# HALF_WAVE_WITH_WITHOUT_FILTER_PCB.net
KiCad netlist of a schematic drawn in EasyEDA
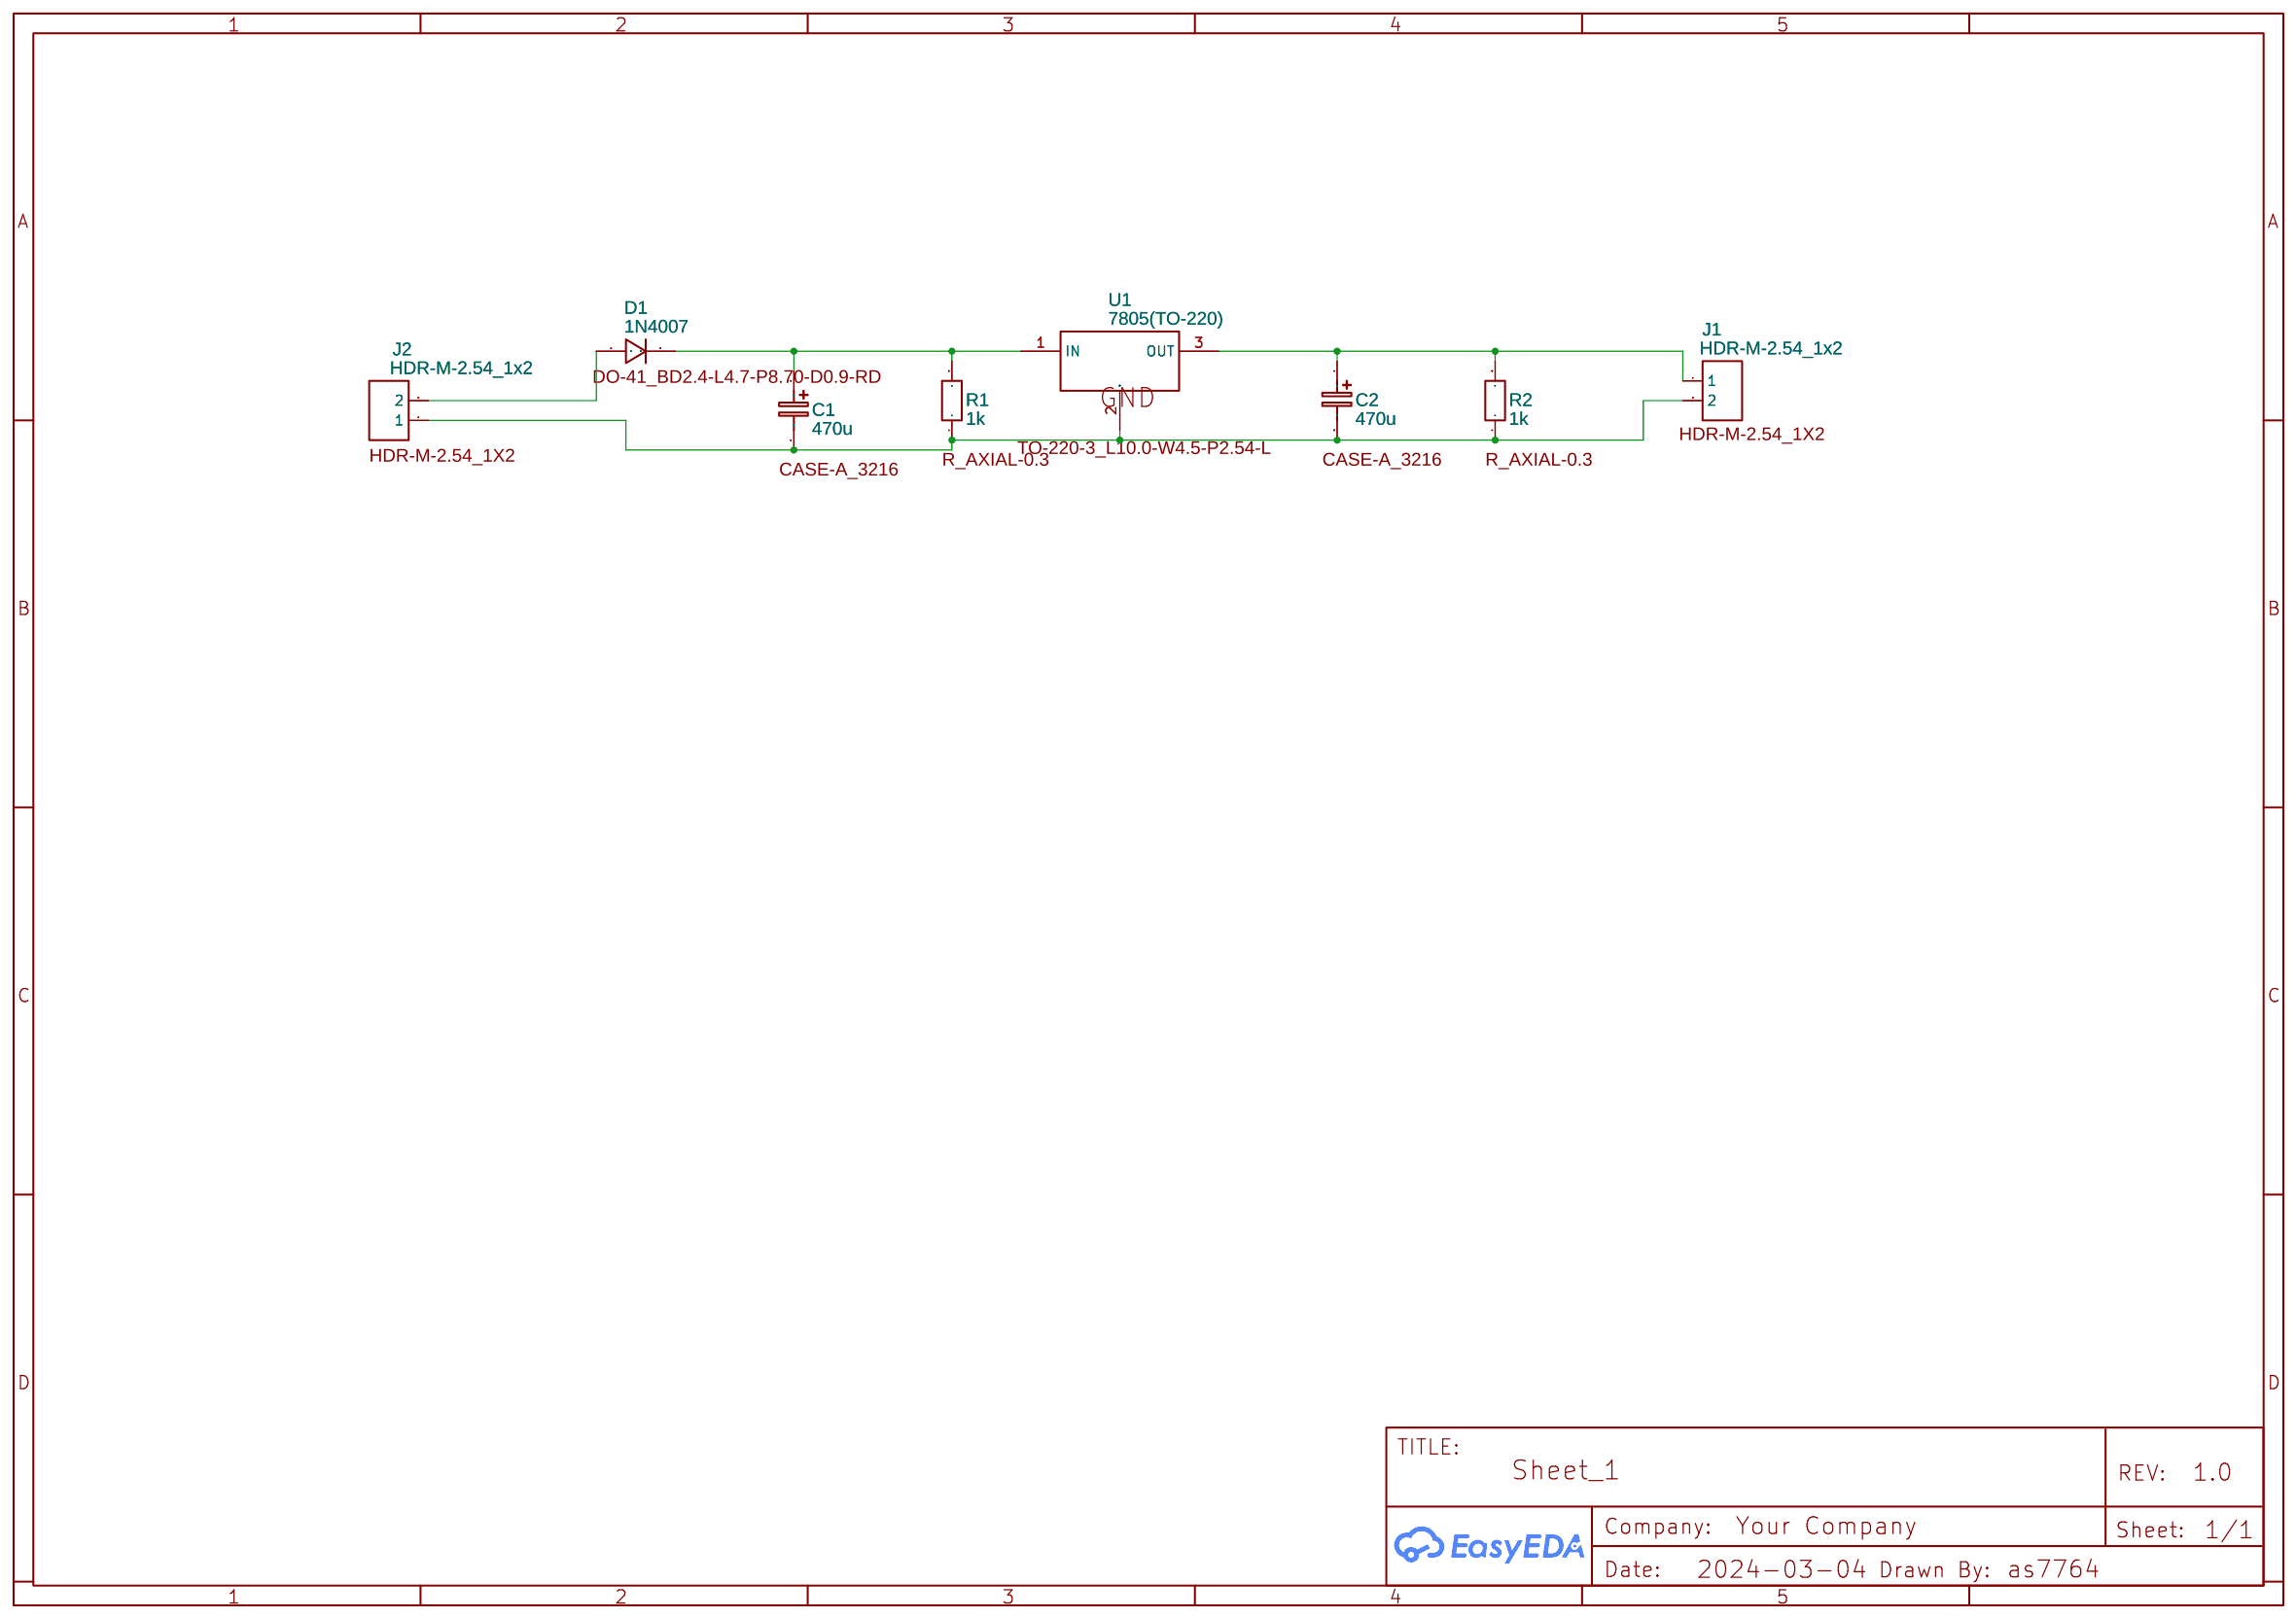
[diagram p0: schematic sheet]

(export (version "E")
  (design (tool "Eeschema 10.0.6"))
  (components
    (comp (ref "C1") (value "470u") (libsource (lib "") (part "C_Tan_SMD_A_EU_1")))
    (comp (ref "C2") (value "470u") (libsource (lib "") (part "C_Tan_SMD_A_EU")))
    (comp (ref "D1")
      (value "1N4007")
      (fields (field (name "Manufacturer") "SEMTECH"))
      (libsource (lib "") (part "1N4007"))
    )
    (comp (ref "J1") (value "HDR-M-2.54_1x2") (libsource (lib "") (part "HDR-M-2.54_1x2")))
    (comp (ref "J2") (value "HDR-M-2.54_1x2") (libsource (lib "") (part "HDR-M-2.54_1x2_1")))
    (comp (ref "R1") (value "1k") (libsource (lib "") (part "R_AXIAL-0.3_EU")))
    (comp (ref "R2") (value "1k") (libsource (lib "") (part "R_AXIAL-0.3_EU")))
    (comp (ref "U1")
      (value "7805(TO-220)")
      (fields
        (field (name "Manufacturer Part") "L7805CV-DG")
        (field (name "Manufacturer") "STMicroelectronics")
      )
      (libsource (lib "") (part "7805(TO-220)"))
    )
  )
  (nets
    (net (code "1") (name "Net-(D1-Pad2)") (class "Default")
      (node (ref "D1") (pin "2") (pinfunction "2_2") (pintype "unspecified"))
      (node (ref "J2") (pin "2") (pinfunction "2_2") (pintype "unspecified"))
    )
    (net (code "2") (name "Net-(U1-GND)") (class "Default")
      (node (ref "C1") (pin "2") (pinfunction "2_2") (pintype "unspecified"))
      (node (ref "C2") (pin "2") (pinfunction "2_2") (pintype "unspecified"))
      (node (ref "J1") (pin "2") (pinfunction "2_2") (pintype "unspecified"))
      (node (ref "J2") (pin "1") (pinfunction "1_1") (pintype "unspecified"))
      (node (ref "R1") (pin "1") (pinfunction "1_1") (pintype "unspecified"))
      (node (ref "R2") (pin "1") (pinfunction "1_1") (pintype "unspecified"))
      (node (ref "U1") (pin "2") (pinfunction "GND_2") (pintype "passive"))
    )
    (net (code "3") (name "Net-(U1-IN)") (class "Default")
      (node (ref "C1") (pin "1") (pinfunction "1_1") (pintype "unspecified"))
      (node (ref "D1") (pin "1") (pinfunction "1_1") (pintype "unspecified"))
      (node (ref "R1") (pin "2") (pinfunction "2_2") (pintype "unspecified"))
      (node (ref "U1") (pin "1") (pinfunction "IN_1") (pintype "passive"))
    )
    (net (code "4") (name "Net-(U1-OUT)") (class "Default")
      (node (ref "C2") (pin "1") (pinfunction "1_1") (pintype "unspecified"))
      (node (ref "J1") (pin "1") (pinfunction "1_1") (pintype "unspecified"))
      (node (ref "R2") (pin "2") (pinfunction "2_2") (pintype "unspecified"))
      (node (ref "U1") (pin "3") (pinfunction "OUT_3") (pintype "passive"))
    )
  )
)
